# ble_minirc.net
KiCad netlist of a schematic drawn in EAGLE
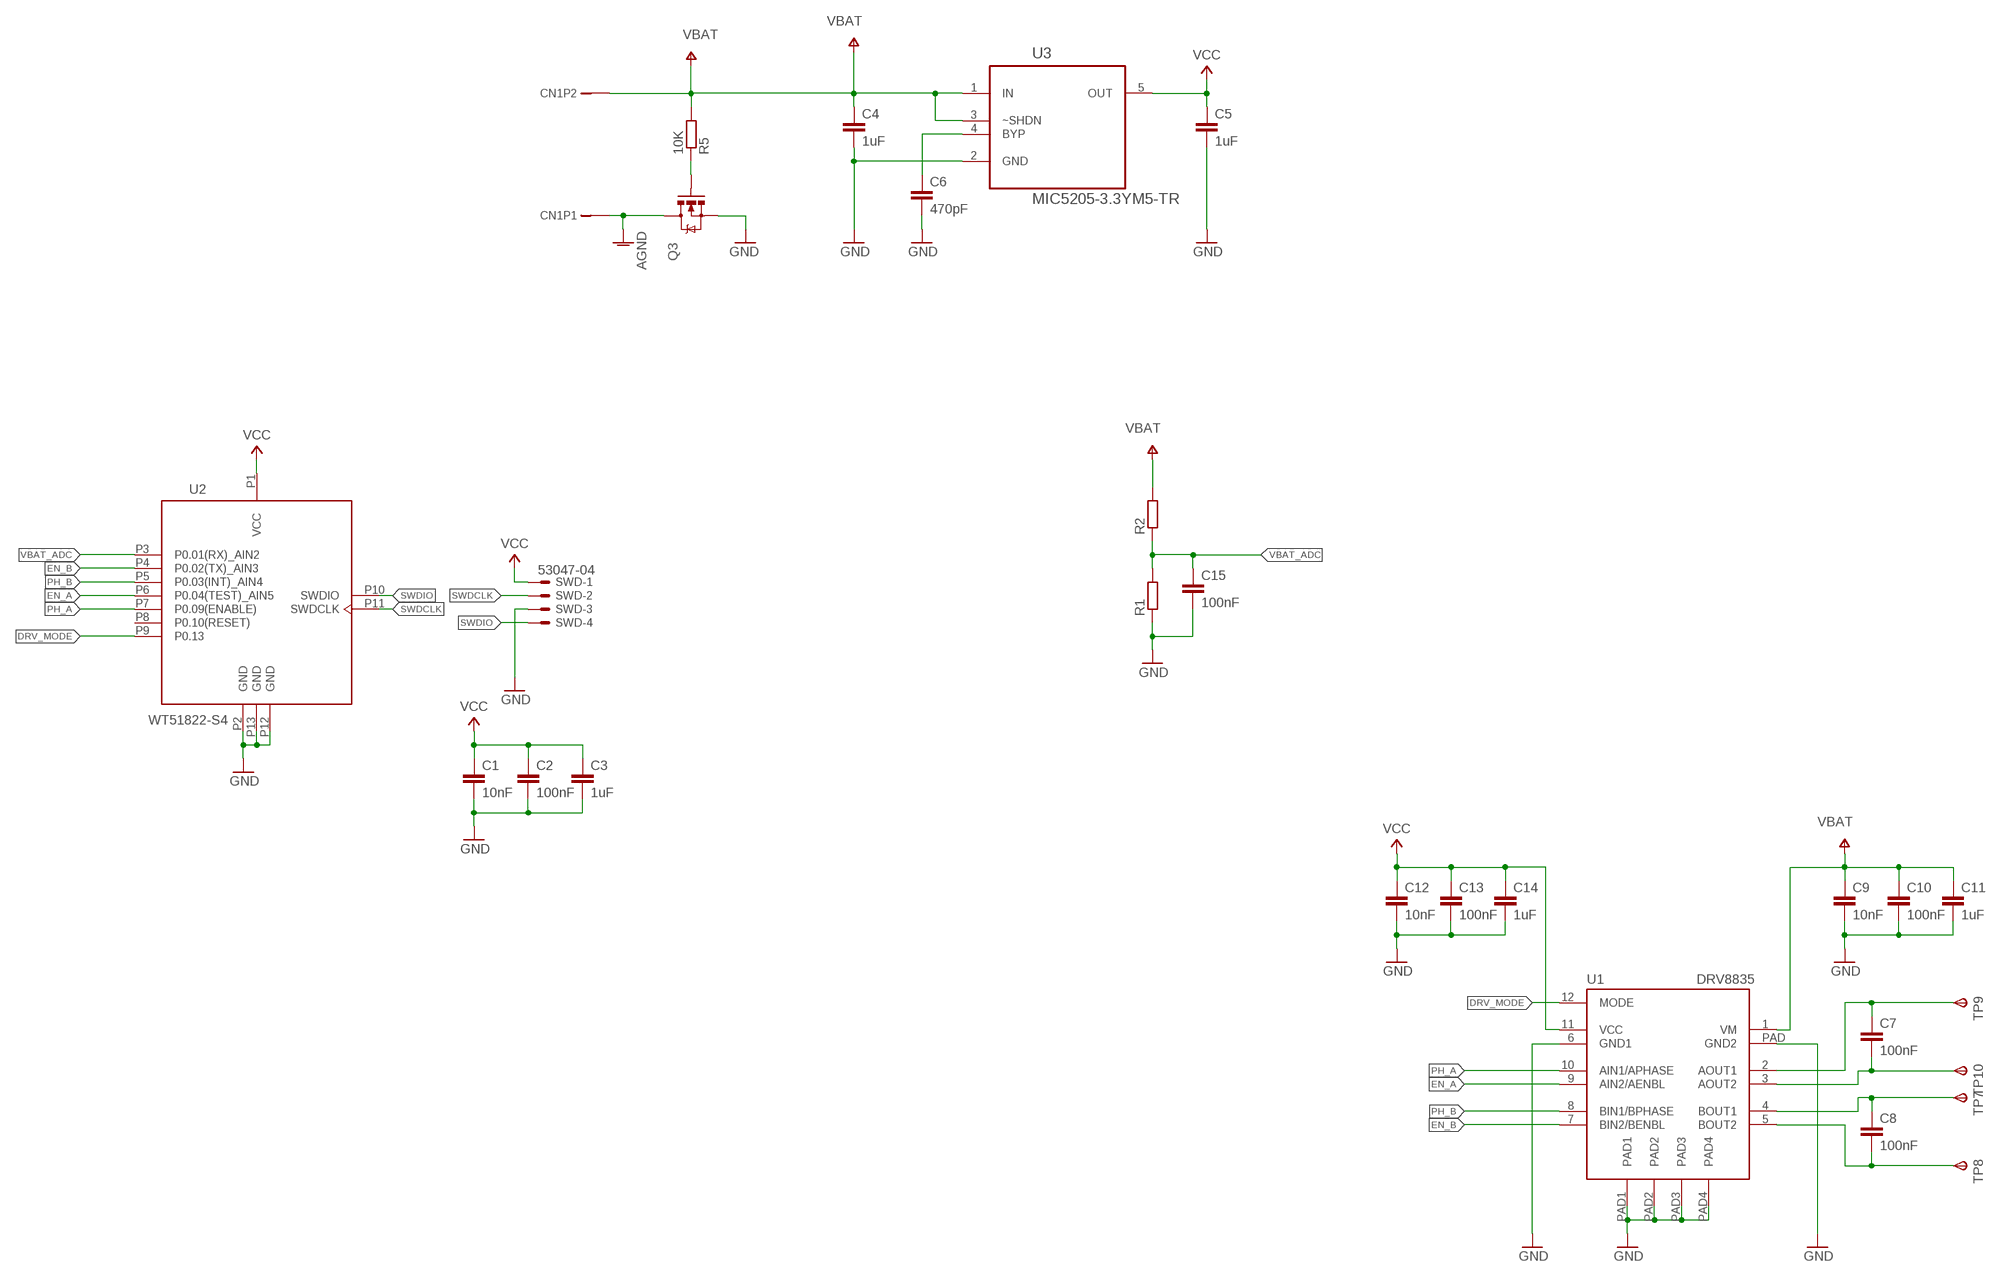
[diagram p0: schematic, sheet 1]

(export (version "E")
  (design (tool "Eeschema 10.0.6"))
  (components
    (comp (ref "C1")
      (value "10nF")
      (footprint "eagle-import:C0603")
      (libsource (lib "eagle-import") (part "C-EUC0603"))
    )
    (comp (ref "C2")
      (value "100nF")
      (footprint "eagle-import:C0603")
      (libsource (lib "eagle-import") (part "C-EUC0603"))
    )
    (comp (ref "C3")
      (value "1uF")
      (footprint "eagle-import:C0603")
      (libsource (lib "eagle-import") (part "C-EUC0603"))
    )
    (comp (ref "C4")
      (value "1uF")
      (footprint "eagle-import:C0603")
      (libsource (lib "eagle-import") (part "C-EUC0603"))
    )
    (comp (ref "C5")
      (value "1uF")
      (footprint "eagle-import:C0603")
      (libsource (lib "eagle-import") (part "C-EUC0603"))
    )
    (comp (ref "C6")
      (value "470pF")
      (footprint "eagle-import:C0603")
      (libsource (lib "eagle-import") (part "C-EUC0603"))
    )
    (comp (ref "C7")
      (value "100nF")
      (footprint "eagle-import:C0603")
      (libsource (lib "eagle-import") (part "C-EUC0603"))
    )
    (comp (ref "C8")
      (value "100nF")
      (footprint "eagle-import:C0603")
      (libsource (lib "eagle-import") (part "C-EUC0603"))
    )
    (comp (ref "C9")
      (value "10nF")
      (footprint "eagle-import:C0603")
      (libsource (lib "eagle-import") (part "C-EUC0603"))
    )
    (comp (ref "C10")
      (value "100nF")
      (footprint "eagle-import:C0603")
      (libsource (lib "eagle-import") (part "C-EUC0603"))
    )
    (comp (ref "C11")
      (value "1uF")
      (footprint "eagle-import:C0603")
      (libsource (lib "eagle-import") (part "C-EUC0603"))
    )
    (comp (ref "C12")
      (value "10nF")
      (footprint "eagle-import:C0603")
      (libsource (lib "eagle-import") (part "C-EUC0603"))
    )
    (comp (ref "C13")
      (value "100nF")
      (footprint "eagle-import:C0603")
      (libsource (lib "eagle-import") (part "C-EUC0603"))
    )
    (comp (ref "C14")
      (value "1uF")
      (footprint "eagle-import:C0603")
      (libsource (lib "eagle-import") (part "C-EUC0603"))
    )
    (comp (ref "C15")
      (value "100nF")
      (footprint "eagle-import:C0603")
      (libsource (lib "eagle-import") (part "C-EUC0603"))
    )
    (comp (ref "CN1")
      (value "B2B-PH-K-S")
      (footprint "eagle-import:B2B-PH-K-S")
      (libsource (lib "eagle-import") (part "B2B-PH-K-S"))
    )
    (comp (ref "Q3")
      (value "MOSFET-NCHANNELSMD")
      (footprint "eagle-import:SOT23-3")
      (libsource (lib "eagle-import") (part "MOSFET-NCHANNELSMD"))
    )
    (comp (ref "R1")
      (value "R-EU_R0603")
      (footprint "eagle-import:R0603")
      (libsource (lib "eagle-import") (part "rcl_334_R-EU_R0603"))
    )
    (comp (ref "R2")
      (value "R-EU_R0603")
      (footprint "eagle-import:R0603")
      (libsource (lib "eagle-import") (part "rcl_334_R-EU_R0603"))
    )
    (comp (ref "R5")
      (value "10K")
      (footprint "eagle-import:R0603")
      (libsource (lib "eagle-import") (part "R-EU_R0603"))
    )
    (comp (ref "SWD")
      (value "53047-04")
      (footprint "eagle-import:53047-04")
      (fields (field (name "MF") "WALDOM/MOLEX") (field (name "MPN") "53047-0410"))
      (libsource (lib "eagle-import") (part "53?-04047"))
    )
    (comp (ref "TP7")
      (value "TPSB1,27")
      (footprint "eagle-import:B1,27")
      (libsource (lib "eagle-import") (part "TPSB1,27"))
    )
    (comp (ref "TP8")
      (value "TPSB1,27")
      (footprint "eagle-import:B1,27")
      (libsource (lib "eagle-import") (part "TPSB1,27"))
    )
    (comp (ref "TP9")
      (value "TPSB1,27")
      (footprint "eagle-import:B1,27")
      (libsource (lib "eagle-import") (part "TPSB1,27"))
    )
    (comp (ref "TP10")
      (value "TPSB1,27")
      (footprint "eagle-import:B1,27")
      (libsource (lib "eagle-import") (part "TPSB1,27"))
    )
    (comp (ref "U1")
      (value "DRV8835")
      (footprint "eagle-import:WSON_2X3")
      (libsource (lib "eagle-import") (part "DRV8835"))
    )
    (comp (ref "U2")
      (value "WT51822-S4")
      (footprint "eagle-import:WT51822-S4AT")
      (libsource (lib "eagle-import") (part "WT51822-S4ATMODULE"))
    )
    (comp (ref "U3")
      (value "MIC5205-3.3YM5-TR")
      (footprint "eagle-import:SOT95P280X145-5N")
      (fields (field (name "MPN") "LT1761ES5-3.3#TRMPBF"))
      (libsource (lib "eagle-import") (part "LT1761ES5-3.3TRMPBF"))
    )
  )
  (nets
    (net (code "1") (name "AGND") (class "Default")
      (node (ref "CN1") (pin "1") (pinfunction "1_1") (pintype "passive"))
      (node (ref "Q3") (pin "3") (pinfunction "D_3") (pintype "passive"))
    )
    (net (code "2") (name "DRV_MODE") (class "Default")
      (node (ref "U1") (pin "12") (pinfunction "MODE_12") (pintype "bidirectional"))
      (node (ref "U2") (pin "P9") (pinfunction "P0.13_P9") (pintype "bidirectional"))
    )
    (net (code "3") (name "EN_A") (class "Default")
      (node (ref "U1") (pin "9") (pinfunction "AIN2/AENBL_9") (pintype "bidirectional"))
      (node (ref "U2") (pin "P6") (pinfunction "P0.04(TEST)_AIN5_P6") (pintype "bidirectional"))
    )
    (net (code "4") (name "EN_B") (class "Default")
      (node (ref "U1") (pin "7") (pinfunction "BIN2/BENBL_7") (pintype "bidirectional"))
      (node (ref "U2") (pin "P4") (pinfunction "P0.02(TX)_AIN3_P4") (pintype "bidirectional"))
    )
    (net (code "5") (name "GND") (class "Default")
      (node (ref "C1") (pin "2") (pinfunction "2_2") (pintype "passive"))
      (node (ref "C10") (pin "2") (pinfunction "2_2") (pintype "passive"))
      (node (ref "C11") (pin "2") (pinfunction "2_2") (pintype "passive"))
      (node (ref "C12") (pin "2") (pinfunction "2_2") (pintype "passive"))
      (node (ref "C13") (pin "2") (pinfunction "2_2") (pintype "passive"))
      (node (ref "C14") (pin "2") (pinfunction "2_2") (pintype "passive"))
      (node (ref "C15") (pin "2") (pinfunction "2_2") (pintype "passive"))
      (node (ref "C2") (pin "2") (pinfunction "2_2") (pintype "passive"))
      (node (ref "C3") (pin "2") (pinfunction "2_2") (pintype "passive"))
      (node (ref "C4") (pin "2") (pinfunction "2_2") (pintype "passive"))
      (node (ref "C5") (pin "2") (pinfunction "2_2") (pintype "passive"))
      (node (ref "C6") (pin "2") (pinfunction "2_2") (pintype "passive"))
      (node (ref "C9") (pin "2") (pinfunction "2_2") (pintype "passive"))
      (node (ref "Q3") (pin "2") (pinfunction "S_2") (pintype "passive"))
      (node (ref "R1") (pin "1") (pinfunction "1_1") (pintype "passive"))
      (node (ref "SWD") (pin "3") (pinfunction "S_3") (pintype "passive"))
      (node (ref "U1") (pin "6") (pinfunction "GND1_6") (pintype "bidirectional"))
      (node (ref "U1") (pin "PAD") (pinfunction "GND2_PAD") (pintype "bidirectional"))
      (node (ref "U1") (pin "PAD1") (pinfunction "PAD1_PAD1") (pintype "bidirectional"))
      (node (ref "U1") (pin "PAD2") (pinfunction "PAD2_PAD2") (pintype "bidirectional"))
      (node (ref "U1") (pin "PAD3") (pinfunction "PAD3_PAD3") (pintype "bidirectional"))
      (node (ref "U1") (pin "PAD4") (pinfunction "PAD4_PAD4") (pintype "bidirectional"))
      (node (ref "U2") (pin "P12") (pinfunction "GND_P12") (pintype "passive"))
      (node (ref "U2") (pin "P13") (pinfunction "GND_P13") (pintype "passive"))
      (node (ref "U2") (pin "P2") (pinfunction "GND_P2") (pintype "passive"))
      (node (ref "U3") (pin "2") (pinfunction "GND_2") (pintype "passive"))
    )
    (net (code "6") (name "Net-(Q3-G)") (class "Default")
      (node (ref "Q3") (pin "1") (pinfunction "G_1") (pintype "passive"))
      (node (ref "R5") (pin "1") (pinfunction "1_1") (pintype "passive"))
    )
    (net (code "7") (name "Net-(TP7-PP)") (class "Default")
      (node (ref "C8") (pin "1") (pinfunction "1_1") (pintype "passive"))
      (node (ref "TP7") (pin "TP") (pinfunction "PP_TP") (pintype "input"))
      (node (ref "U1") (pin "4") (pinfunction "BOUT1_4") (pintype "bidirectional"))
    )
    (net (code "8") (name "Net-(TP8-PP)") (class "Default")
      (node (ref "C8") (pin "2") (pinfunction "2_2") (pintype "passive"))
      (node (ref "TP8") (pin "TP") (pinfunction "PP_TP") (pintype "input"))
      (node (ref "U1") (pin "5") (pinfunction "BOUT2_5") (pintype "bidirectional"))
    )
    (net (code "9") (name "Net-(TP9-PP)") (class "Default")
      (node (ref "C7") (pin "1") (pinfunction "1_1") (pintype "passive"))
      (node (ref "TP9") (pin "TP") (pinfunction "PP_TP") (pintype "input"))
      (node (ref "U1") (pin "2") (pinfunction "AOUT1_2") (pintype "bidirectional"))
    )
    (net (code "10") (name "Net-(TP10-PP)") (class "Default")
      (node (ref "C7") (pin "2") (pinfunction "2_2") (pintype "passive"))
      (node (ref "TP10") (pin "TP") (pinfunction "PP_TP") (pintype "input"))
      (node (ref "U1") (pin "3") (pinfunction "AOUT2_3") (pintype "bidirectional"))
    )
    (net (code "11") (name "Net-(U3-BYP)") (class "Default")
      (node (ref "C6") (pin "1") (pinfunction "1_1") (pintype "passive"))
      (node (ref "U3") (pin "4") (pinfunction "BYP_4") (pintype "passive"))
    )
    (net (code "12") (name "PH_A") (class "Default")
      (node (ref "U1") (pin "10") (pinfunction "AIN1/APHASE_10") (pintype "bidirectional"))
      (node (ref "U2") (pin "P7") (pinfunction "P0.09(ENABLE)_P7") (pintype "bidirectional"))
    )
    (net (code "13") (name "PH_B") (class "Default")
      (node (ref "U1") (pin "8") (pinfunction "BIN1/BPHASE_8") (pintype "bidirectional"))
      (node (ref "U2") (pin "P5") (pinfunction "P0.03(INT)_AIN4_P5") (pintype "bidirectional"))
    )
    (net (code "14") (name "SWDCLK") (class "Default")
      (node (ref "SWD") (pin "2") (pinfunction "S_2") (pintype "passive"))
      (node (ref "U2") (pin "P11") (pinfunction "SWDCLK_P11") (pintype "input"))
    )
    (net (code "15") (name "SWDIO") (class "Default")
      (node (ref "SWD") (pin "4") (pinfunction "S_4") (pintype "passive"))
      (node (ref "U2") (pin "P10") (pinfunction "SWDIO_P10") (pintype "bidirectional"))
    )
    (net (code "16") (name "VBAT") (class "Default")
      (node (ref "C10") (pin "1") (pinfunction "1_1") (pintype "passive"))
      (node (ref "C11") (pin "1") (pinfunction "1_1") (pintype "passive"))
      (node (ref "C4") (pin "1") (pinfunction "1_1") (pintype "passive"))
      (node (ref "C9") (pin "1") (pinfunction "1_1") (pintype "passive"))
      (node (ref "CN1") (pin "2") (pinfunction "1_2") (pintype "passive"))
      (node (ref "R2") (pin "2") (pinfunction "2_2") (pintype "passive"))
      (node (ref "R5") (pin "2") (pinfunction "2_2") (pintype "passive"))
      (node (ref "U1") (pin "1") (pinfunction "VM_1") (pintype "bidirectional"))
      (node (ref "U3") (pin "1") (pinfunction "IN_1") (pintype "power_in"))
      (node (ref "U3") (pin "3") (pinfunction "~{SHDN}_3") (pintype "input"))
    )
    (net (code "17") (name "VBAT_ADC") (class "Default")
      (node (ref "C15") (pin "1") (pinfunction "1_1") (pintype "passive"))
      (node (ref "R1") (pin "2") (pinfunction "2_2") (pintype "passive"))
      (node (ref "R2") (pin "1") (pinfunction "1_1") (pintype "passive"))
      (node (ref "U2") (pin "P3") (pinfunction "P0.01(RX)_AIN2_P3") (pintype "bidirectional"))
    )
    (net (code "18") (name "VCC") (class "Default")
      (node (ref "C1") (pin "1") (pinfunction "1_1") (pintype "passive"))
      (node (ref "C12") (pin "1") (pinfunction "1_1") (pintype "passive"))
      (node (ref "C13") (pin "1") (pinfunction "1_1") (pintype "passive"))
      (node (ref "C14") (pin "1") (pinfunction "1_1") (pintype "passive"))
      (node (ref "C2") (pin "1") (pinfunction "1_1") (pintype "passive"))
      (node (ref "C3") (pin "1") (pinfunction "1_1") (pintype "passive"))
      (node (ref "C5") (pin "1") (pinfunction "1_1") (pintype "passive"))
      (node (ref "SWD") (pin "1") (pinfunction "S_1") (pintype "passive"))
      (node (ref "U1") (pin "11") (pinfunction "VCC_11") (pintype "bidirectional"))
      (node (ref "U2") (pin "P1") (pinfunction "VCC_P1") (pintype "passive"))
      (node (ref "U3") (pin "5") (pinfunction "OUT_5") (pintype "passive"))
    )
    (net (code "19") (name "unconnected-(U2-P0.10(RESET)-PadP8)") (class "Default")
      (node (ref "U2") (pin "P8") (pinfunction "P0.10(RESET)_P8") (pintype "bidirectional"))
    )
  )
)
